# RPI_Hat_ID.net
KiCad netlist of a schematic drawn in Altium Designer
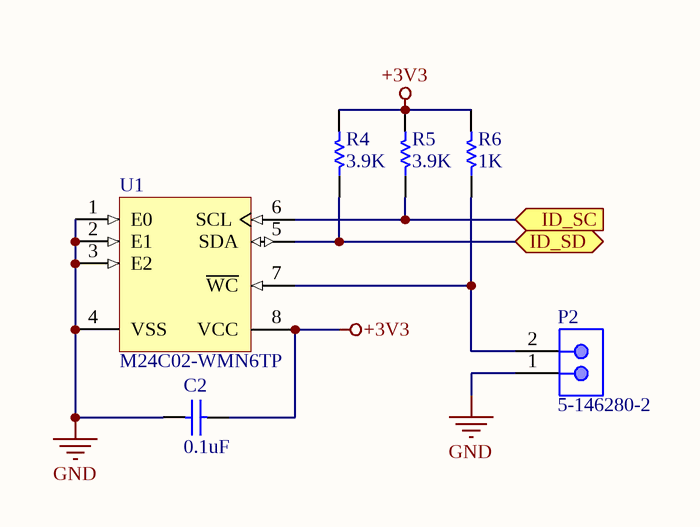
[diagram p0: RPI Hat ID.SchDoc]

(export (version "E")
  (design (tool "Eeschema 10.0.6"))
  (components
    (comp (ref "C2")
      (value "0.1uF")
      (footprint "CAPC1608X87X35NL15T15")
      (fields (field (name "PART NUMBER") "C0603X104K5RACTU") (field (name "MANUFACTURER") "Kemet"))
      (libsource (lib "Altium Content Vault") (part "CAP"))
    )
    (comp (ref "P2")
      (value "5-146280-2")
      (footprint "TECO-5-146280-2_V")
      (fields (field (name "MANUFACTURER") "TE Connectivity"))
      (libsource (lib "Altium Content Vault") (part "CN-1P-M-R2"))
    )
    (comp (ref "R4")
      (value "3.9K")
      (footprint "RESC1608X55X30ML15T15")
      (fields (field (name "PART NUMBER") "ERJ-3EKF1001V") (field (name "MANUFACTURER") "Panasonic"))
      (libsource (lib "Altium Content Vault") (part "RES"))
    )
    (comp (ref "R5")
      (value "3.9K")
      (footprint "RESC1608X55X30ML15T15")
      (fields (field (name "PART NUMBER") "ERJ-3EKF1001V") (field (name "MANUFACTURER") "Panasonic"))
      (libsource (lib "Altium Content Vault") (part "RES"))
    )
    (comp (ref "R6")
      (value "1K")
      (footprint "RESC1608X55X30ML15T15")
      (fields (field (name "PART NUMBER") "ERJ-3EKF1001V") (field (name "MANUFACTURER") "Panasonic"))
      (libsource (lib "Altium Content Vault") (part "RES"))
    )
    (comp (ref "U1")
      (value "M24C02-WMN6TP")
      (footprint "STM-M24C02-WMN6TP-8_M")
      (description "EEPROM Serial-I2C, 2Kbit, 2.5 to 5.5 V, 400 kHz, 8-Pin SO, -40 to 85 degC, RoHS, Tape and Reel")
      (fields (field (name "MANUFACTURER") "STMicroelectronics"))
      (libsource (lib "Altium Content Vault") (part "STM-M24C02-WMN6TP-8"))
    )
  )
  (nets
    (net (code "1") (name "+3V3") (class "Default")
      (node (ref "C2") (pin "1") (pinfunction "1_1") (pintype "passive"))
      (node (ref "R4") (pin "2") (pinfunction "2_2") (pintype "passive"))
      (node (ref "R5") (pin "2") (pinfunction "2_2") (pintype "passive"))
      (node (ref "R6") (pin "2") (pinfunction "2_2") (pintype "passive"))
      (node (ref "U1") (pin "8") (pinfunction "VCC_8") (pintype "power_in"))
    )
    (net (code "2") (name "/ID_SC") (class "Default")
      (node (ref "R5") (pin "1") (pinfunction "1_1") (pintype "passive"))
      (node (ref "U1") (pin "6") (pinfunction "SCL_6") (pintype "input"))
    )
    (net (code "3") (name "/ID_SD") (class "Default")
      (node (ref "R4") (pin "1") (pinfunction "1_1") (pintype "passive"))
      (node (ref "U1") (pin "5") (pinfunction "SDA_5") (pintype "bidirectional"))
    )
    (net (code "4") (name "GND") (class "Default")
      (node (ref "C2") (pin "2") (pinfunction "2_2") (pintype "passive"))
      (node (ref "P2") (pin "1") (pinfunction "1_1") (pintype "passive"))
      (node (ref "U1") (pin "1") (pinfunction "E0_1") (pintype "input"))
      (node (ref "U1") (pin "2") (pinfunction "E1_2") (pintype "input"))
      (node (ref "U1") (pin "3") (pinfunction "E2_3") (pintype "input"))
      (node (ref "U1") (pin "4") (pinfunction "VSS_4") (pintype "power_in"))
    )
    (net (code "5") (name "Net-(U1-~{WC})") (class "Default")
      (node (ref "P2") (pin "2") (pinfunction "2_2") (pintype "passive"))
      (node (ref "R6") (pin "1") (pinfunction "1_1") (pintype "passive"))
      (node (ref "U1") (pin "7") (pinfunction "~{WC}_7") (pintype "input"))
    )
  )
)
